# JTAG2SW.net
KiCad netlist of a schematic drawn in Altium Designer
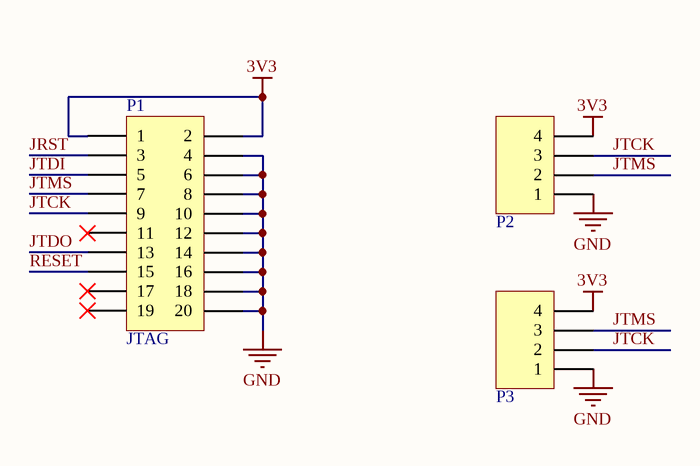
[diagram p0: JTAG2SW.SchDoc]

(export (version "E")
  (design (tool "Eeschema 10.0.6"))
  (components
    (comp (ref "P1")
      (value "JTAG")
      (footprint "HDR10X2_SMT")
      (description "Header, 10-Pin")
      (fields (field (name "PUBLISHER") "Altium Limited"))
      (libsource (lib "fszhang") (part "Header 10X2"))
    )
    (comp (ref "P2")
      (value "Header 4")
      (footprint "HDR4X1_TP")
      (description "接插件")
      (fields (field (name "PUBLISHER") "Altium Limited"))
      (libsource (lib "fszhang") (part "Header 4"))
    )
    (comp (ref "P3")
      (value "Header 4")
      (footprint "HDR4X1_TP")
      (description "接插件")
      (fields (field (name "PUBLISHER") "Altium Limited"))
      (libsource (lib "fszhang") (part "Header 4"))
    )
  )
  (nets
    (net (code "1") (name "/JRST") (class "Default")
      (node (ref "P1") (pin "3") (pinfunction "3_3") (pintype "passive"))
    )
    (net (code "2") (name "/JTCK") (class "Default")
      (node (ref "P1") (pin "9") (pinfunction "9_9") (pintype "passive"))
      (node (ref "P2") (pin "3") (pinfunction "3_3") (pintype "passive"))
      (node (ref "P3") (pin "2") (pinfunction "2_2") (pintype "passive"))
    )
    (net (code "3") (name "/JTDI") (class "Default")
      (node (ref "P1") (pin "5") (pinfunction "5_5") (pintype "passive"))
    )
    (net (code "4") (name "/JTDO") (class "Default")
      (node (ref "P1") (pin "13") (pinfunction "13_13") (pintype "passive"))
    )
    (net (code "5") (name "/JTMS") (class "Default")
      (node (ref "P1") (pin "7") (pinfunction "7_7") (pintype "passive"))
      (node (ref "P2") (pin "2") (pinfunction "2_2") (pintype "passive"))
      (node (ref "P3") (pin "3") (pinfunction "3_3") (pintype "passive"))
    )
    (net (code "6") (name "/RESET") (class "Default")
      (node (ref "P1") (pin "15") (pinfunction "15_15") (pintype "passive"))
    )
    (net (code "7") (name "3V3") (class "Default")
      (node (ref "P1") (pin "1") (pinfunction "1_1") (pintype "passive"))
      (node (ref "P1") (pin "2") (pinfunction "2_2") (pintype "passive"))
      (node (ref "P2") (pin "4") (pinfunction "4_4") (pintype "passive"))
      (node (ref "P3") (pin "4") (pinfunction "4_4") (pintype "passive"))
    )
    (net (code "8") (name "GND") (class "Default")
      (node (ref "P1") (pin "10") (pinfunction "10_10") (pintype "passive"))
      (node (ref "P1") (pin "12") (pinfunction "12_12") (pintype "passive"))
      (node (ref "P1") (pin "14") (pinfunction "14_14") (pintype "passive"))
      (node (ref "P1") (pin "16") (pinfunction "16_16") (pintype "passive"))
      (node (ref "P1") (pin "18") (pinfunction "18_18") (pintype "passive"))
      (node (ref "P1") (pin "20") (pinfunction "20_20") (pintype "passive"))
      (node (ref "P1") (pin "4") (pinfunction "4_4") (pintype "passive"))
      (node (ref "P1") (pin "6") (pinfunction "6_6") (pintype "passive"))
      (node (ref "P1") (pin "8") (pinfunction "8_8") (pintype "passive"))
      (node (ref "P2") (pin "1") (pinfunction "1_1") (pintype "passive"))
      (node (ref "P3") (pin "1") (pinfunction "1_1") (pintype "passive"))
    )
    (net (code "9") (name "unconnected-(P1-Pad11)") (class "Default")
      (node (ref "P1") (pin "11") (pinfunction "11_11") (pintype "passive+no_connect"))
    )
    (net (code "10") (name "unconnected-(P1-Pad17)") (class "Default")
      (node (ref "P1") (pin "17") (pinfunction "17_17") (pintype "passive+no_connect"))
    )
    (net (code "11") (name "unconnected-(P1-Pad19)") (class "Default")
      (node (ref "P1") (pin "19") (pinfunction "19_19") (pintype "passive+no_connect"))
    )
  )
)
